# board1.net
KiCad netlist of a schematic drawn in Altium Designer
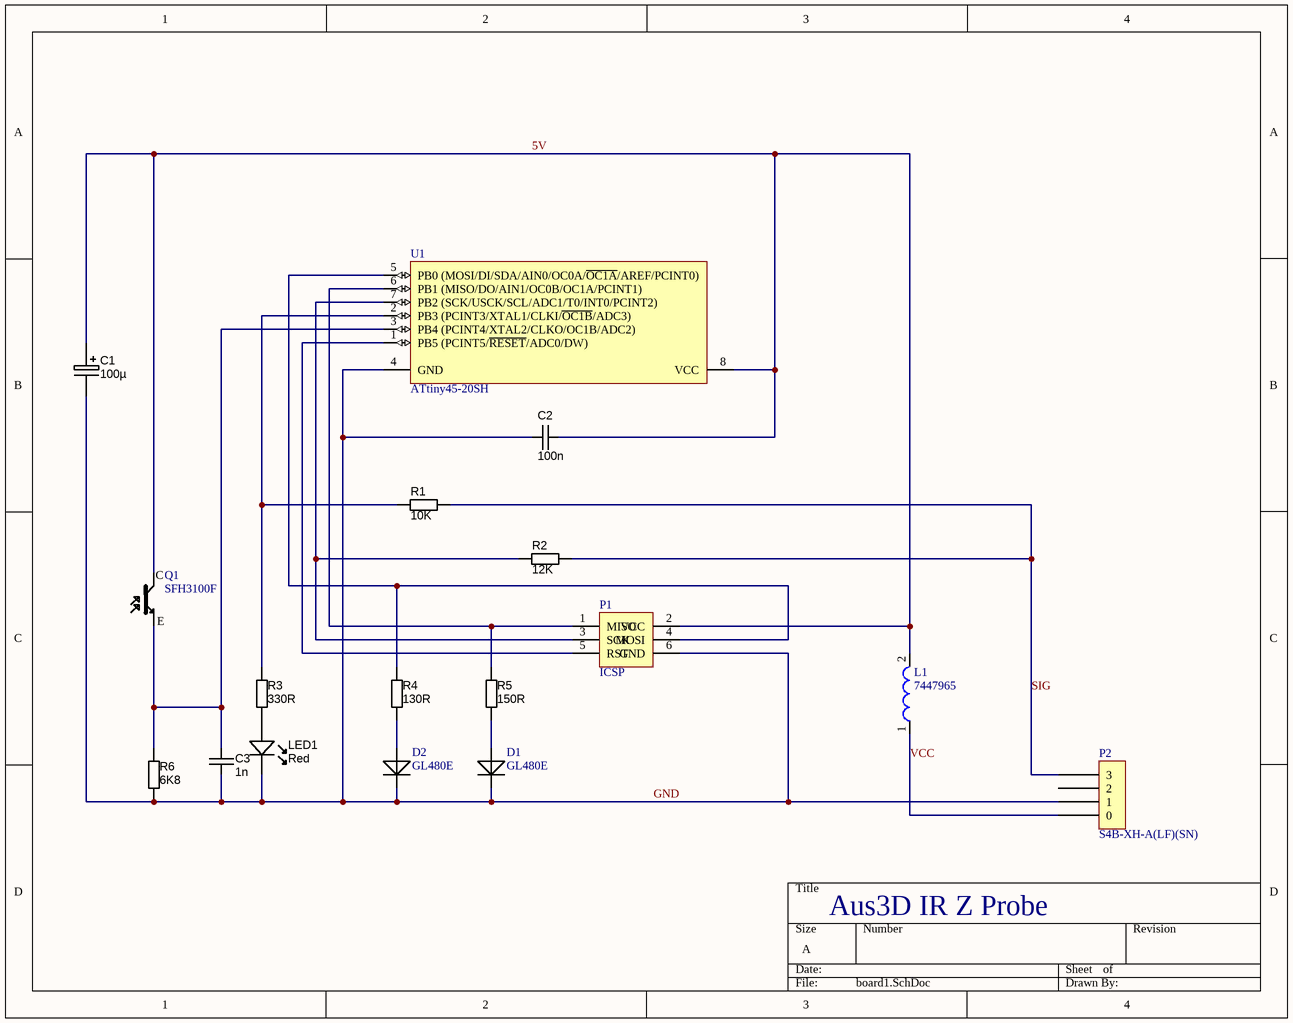
[diagram p0: board1.SchDoc]

(export (version "E")
  (design (tool "Eeschema 10.0.6"))
  (components
    (comp (ref "C1")
      (value "100µ")
      (footprint "6.3-DIA-CAP")
      (description "Capacitor THD Electrolytic 100uF 20% 16V Radial")
      (fields (field (name "TOLERANCE") "±20%") (field (name "MANUFACTURER") "Panasonic - ECG"))
      (libsource (lib "PBL - Capacitors") (part "CAPE_100u_16V_THD"))
    )
    (comp (ref "C2")
      (value "100n")
      (footprint "CAPC1005X55N")
      (description "Capacitor SMD Cer 100nF 10% 16V X5R 0402")
      (fields (field (name "TOLERANCE") "±10%"))
      (libsource (lib "PBL - Capacitors") (part "CAPC_100n_0402_X5R_16V_10%"))
    )
    (comp (ref "C3")
      (value "1n")
      (footprint "CAPC1005X55N")
      (description "Capacitor SMD Cer 1nF 10% 16V X7R 0402")
      (fields (field (name "TOLERANCE") "±10%"))
      (libsource (lib "PBL - Capacitors") (part "CAPC_1n_0402_X7R_16V_10%"))
    )
    (comp (ref "D1")
      (value "GL480E")
      (footprint "LED-2.54spacing")
      (libsource (lib "Schlib1") (part "GL480E"))
    )
    (comp (ref "D2")
      (value "GL480E")
      (footprint "LED-2.54spacing")
      (libsource (lib "Schlib1") (part "GL480E"))
    )
    (comp (ref "L1")
      (value "7447965")
      (footprint "SMD-0603")
      (description "SMD-Multilayer Inductor WE-MI, L = 1.00 µH")
      (libsource (lib "Wuerth Elektronik Filter Inductor") (part "7447965"))
    )
    (comp (ref "LED1")
      (value "Red")
      (footprint "LED-0603-RED")
      (description "LED 0603 SMD Hyper Red 630nm 220mcd 20mA")
      (libsource (lib "PBL - Light Sources") (part "LED_SMD_Red_0603_220mcd"))
    )
    (comp (ref "P1")
      (value "ICSP")
      (footprint "HDR2X3")
      (description "Header, 3-Pin, Dual row")
      (fields (field (name "PUBLISHER") "Altium Limited"))
      (libsource (lib "Miscellaneous Connectors") (part "Header 3X2"))
    )
    (comp (ref "P2")
      (value "S4B-XH-A(LF)(SN)")
      (footprint "S4B-XH-A(LF)(SN)")
      (libsource (lib "Schlib1") (part "S4B-XH-A(LF)(SN)"))
    )
    (comp (ref "Q1")
      (value "SFH3100F")
      (footprint "SFH3100F-footprint")
      (description "GL480E")
      (libsource (lib "Schlib1") (part "SFH3100F"))
    )
    (comp (ref "R1")
      (value "10K")
      (footprint "RESC1608X55N")
      (description "Resistor SMD chip 2.2k Ohm 0.1W 5% 0603")
      (fields (field (name "TOLERANCE") "±5%") (field (name "Comment") "Thick Film"))
      (libsource (lib "PBL - Resistors") (part "RES_2K2_0603_5%"))
    )
    (comp (ref "R2")
      (value "12K")
      (footprint "RESC1608X55N")
      (description "Resistor SMD chip 2.2k Ohm 0.1W 5% 0603")
      (fields (field (name "TOLERANCE") "±5%") (field (name "Comment") "Thick Film"))
      (libsource (lib "PBL - Resistors") (part "RES_2K2_0603_5%"))
    )
    (comp (ref "R3")
      (value "330R")
      (footprint "RESC1608X55N")
      (description "Resistor SMD chip 330 Ohm 0.1W 5% 0603")
      (fields (field (name "TOLERANCE") "±5%") (field (name "Comment") "Thick Film"))
      (libsource (lib "PBL - Resistors") (part "RES_330R_0603_5%"))
    )
    (comp (ref "R4")
      (value "130R")
      (footprint "RESC1608X55N")
      (description "Resistor SMD chip 2.2k Ohm 0.1W 5% 0603")
      (fields (field (name "TOLERANCE") "±5%") (field (name "Comment") "Thick Film"))
      (libsource (lib "") (part "RES_2K2_0603_5%_1"))
    )
    (comp (ref "R5")
      (value "150R")
      (footprint "RESC1608X55N")
      (description "Resistor SMD chip 2.2k Ohm 0.1W 5% 0603")
      (fields (field (name "TOLERANCE") "±5%") (field (name "Comment") "Thick Film"))
      (libsource (lib "") (part "RES_2K2_0603_5%_1"))
    )
    (comp (ref "R6")
      (value "6K8")
      (footprint "RESC1608X55N")
      (description "Resistor SMD chip 2.2k Ohm 0.1W 5% 0603")
      (fields (field (name "TOLERANCE") "±5%") (field (name "Comment") "Thick Film"))
      (libsource (lib "") (part "RES_2K2_0603_5%_1"))
    )
    (comp (ref "U1")
      (value "ATtiny45-20SH")
      (footprint "8S2_N")
      (libsource (lib "Atmel Microcontroller tinyAVR") (part "ATtiny45-20SH"))
    )
  )
  (nets
    (net (code "1") (name "/5V") (class "Default")
      (node (ref "C1") (pin "1") (pintype "passive"))
      (node (ref "C2") (pin "2") (pintype "passive"))
      (node (ref "L1") (pin "2") (pinfunction "2_2") (pintype "passive"))
      (node (ref "P1") (pin "2") (pinfunction "VCC_2") (pintype "passive"))
      (node (ref "Q1") (pin "1") (pinfunction "1_1") (pintype "passive"))
      (node (ref "U1") (pin "8") (pinfunction "VCC_8") (pintype "power_in"))
    )
    (net (code "2") (name "/GND") (class "Default")
      (node (ref "C1") (pin "2") (pintype "passive"))
      (node (ref "C2") (pin "1") (pintype "passive"))
      (node (ref "C3") (pin "2") (pintype "passive"))
      (node (ref "D1") (pin "1") (pinfunction "1_1") (pintype "passive"))
      (node (ref "D2") (pin "1") (pinfunction "1_1") (pintype "passive"))
      (node (ref "LED1") (pin "K") (pinfunction "K_K") (pintype "passive"))
      (node (ref "P1") (pin "6") (pinfunction "GND_6") (pintype "passive"))
      (node (ref "P2") (pin "1") (pinfunction "1_1") (pintype "passive"))
      (node (ref "R6") (pin "1") (pinfunction "1_1") (pintype "passive"))
      (node (ref "U1") (pin "4") (pinfunction "GND_4") (pintype "power_in"))
    )
    (net (code "3") (name "/SIG") (class "Default")
      (node (ref "P2") (pin "3") (pinfunction "3_3") (pintype "passive"))
      (node (ref "R1") (pin "1") (pinfunction "1_1") (pintype "passive"))
      (node (ref "R2") (pin "1") (pinfunction "1_1") (pintype "passive"))
    )
    (net (code "4") (name "/VCC") (class "Default")
      (node (ref "L1") (pin "1") (pinfunction "1_1") (pintype "passive"))
      (node (ref "P2") (pin "0") (pinfunction "0_0") (pintype "passive"))
    )
    (net (code "5") (name "Net-(D1-Pad2)") (class "Default")
      (node (ref "D1") (pin "2") (pinfunction "2_2") (pintype "passive"))
      (node (ref "R5") (pin "1") (pinfunction "1_1") (pintype "passive"))
    )
    (net (code "6") (name "Net-(D2-Pad2)") (class "Default")
      (node (ref "D2") (pin "2") (pinfunction "2_2") (pintype "passive"))
      (node (ref "R4") (pin "1") (pinfunction "1_1") (pintype "passive"))
    )
    (net (code "7") (name "Net-(LED1-PadA)") (class "Default")
      (node (ref "LED1") (pin "A") (pinfunction "A_A") (pintype "passive"))
      (node (ref "R3") (pin "2") (pinfunction "2_2") (pintype "passive"))
    )
    (net (code "8") (name "Net-(P1-MISO)") (class "Default")
      (node (ref "P1") (pin "1") (pinfunction "MISO_1") (pintype "passive"))
      (node (ref "R5") (pin "2") (pinfunction "2_2") (pintype "passive"))
      (node (ref "U1") (pin "6") (pinfunction "PB1_(MISO/DO/AIN1/OC0B/OC1A/PCINT1)_6") (pintype "bidirectional"))
    )
    (net (code "9") (name "Net-(P1-MOSI)") (class "Default")
      (node (ref "P1") (pin "4") (pinfunction "MOSI_4") (pintype "passive"))
      (node (ref "R4") (pin "2") (pinfunction "2_2") (pintype "passive"))
      (node (ref "U1") (pin "5") (pinfunction "PB0_(MOSI/DI/SDA/AIN0/OC0A/~{OC1A}/AREF/PCINT0)_5") (pintype "bidirectional"))
    )
    (net (code "10") (name "Net-(P1-RST)") (class "Default")
      (node (ref "P1") (pin "5") (pinfunction "RST_5") (pintype "passive"))
      (node (ref "U1") (pin "1") (pinfunction "PB5_(PCINT5/~{RESET}/ADC0/DW)_1") (pintype "bidirectional"))
    )
    (net (code "11") (name "Net-(P1-SCK)") (class "Default")
      (node (ref "P1") (pin "3") (pinfunction "SCK_3") (pintype "passive"))
      (node (ref "R2") (pin "2") (pinfunction "2_2") (pintype "passive"))
      (node (ref "U1") (pin "7") (pinfunction "PB2_(SCK/USCK/SCL/ADC1/T0/INT0/PCINT2)_7") (pintype "bidirectional"))
    )
    (net (code "12") (name "Net-(U1-PB3_(PCINT3{slash}XTAL1{slash}CLKI{slash}~{OC1B}{slash}ADC3))") (class "Default")
      (node (ref "R1") (pin "2") (pinfunction "2_2") (pintype "passive"))
      (node (ref "R3") (pin "1") (pinfunction "1_1") (pintype "passive"))
      (node (ref "U1") (pin "2") (pinfunction "PB3_(PCINT3/XTAL1/CLKI/~{OC1B}/ADC3)_2") (pintype "bidirectional"))
    )
    (net (code "13") (name "Net-(U1-PB4_(PCINT4{slash}XTAL2{slash}CLKO{slash}OC1B{slash}ADC2))") (class "Default")
      (node (ref "C3") (pin "1") (pintype "passive"))
      (node (ref "Q1") (pin "2") (pinfunction "2_2") (pintype "passive"))
      (node (ref "R6") (pin "2") (pinfunction "2_2") (pintype "passive"))
      (node (ref "U1") (pin "3") (pinfunction "PB4_(PCINT4/XTAL2/CLKO/OC1B/ADC2)_3") (pintype "bidirectional"))
    )
    (net (code "14") (name "unconnected-(P2-Pad2)") (class "Default")
      (node (ref "P2") (pin "2") (pinfunction "2_2") (pintype "passive"))
    )
  )
)
